# Protoboard_MX4-7-6-ESP12.net
KiCad netlist of a schematic drawn in EAGLE
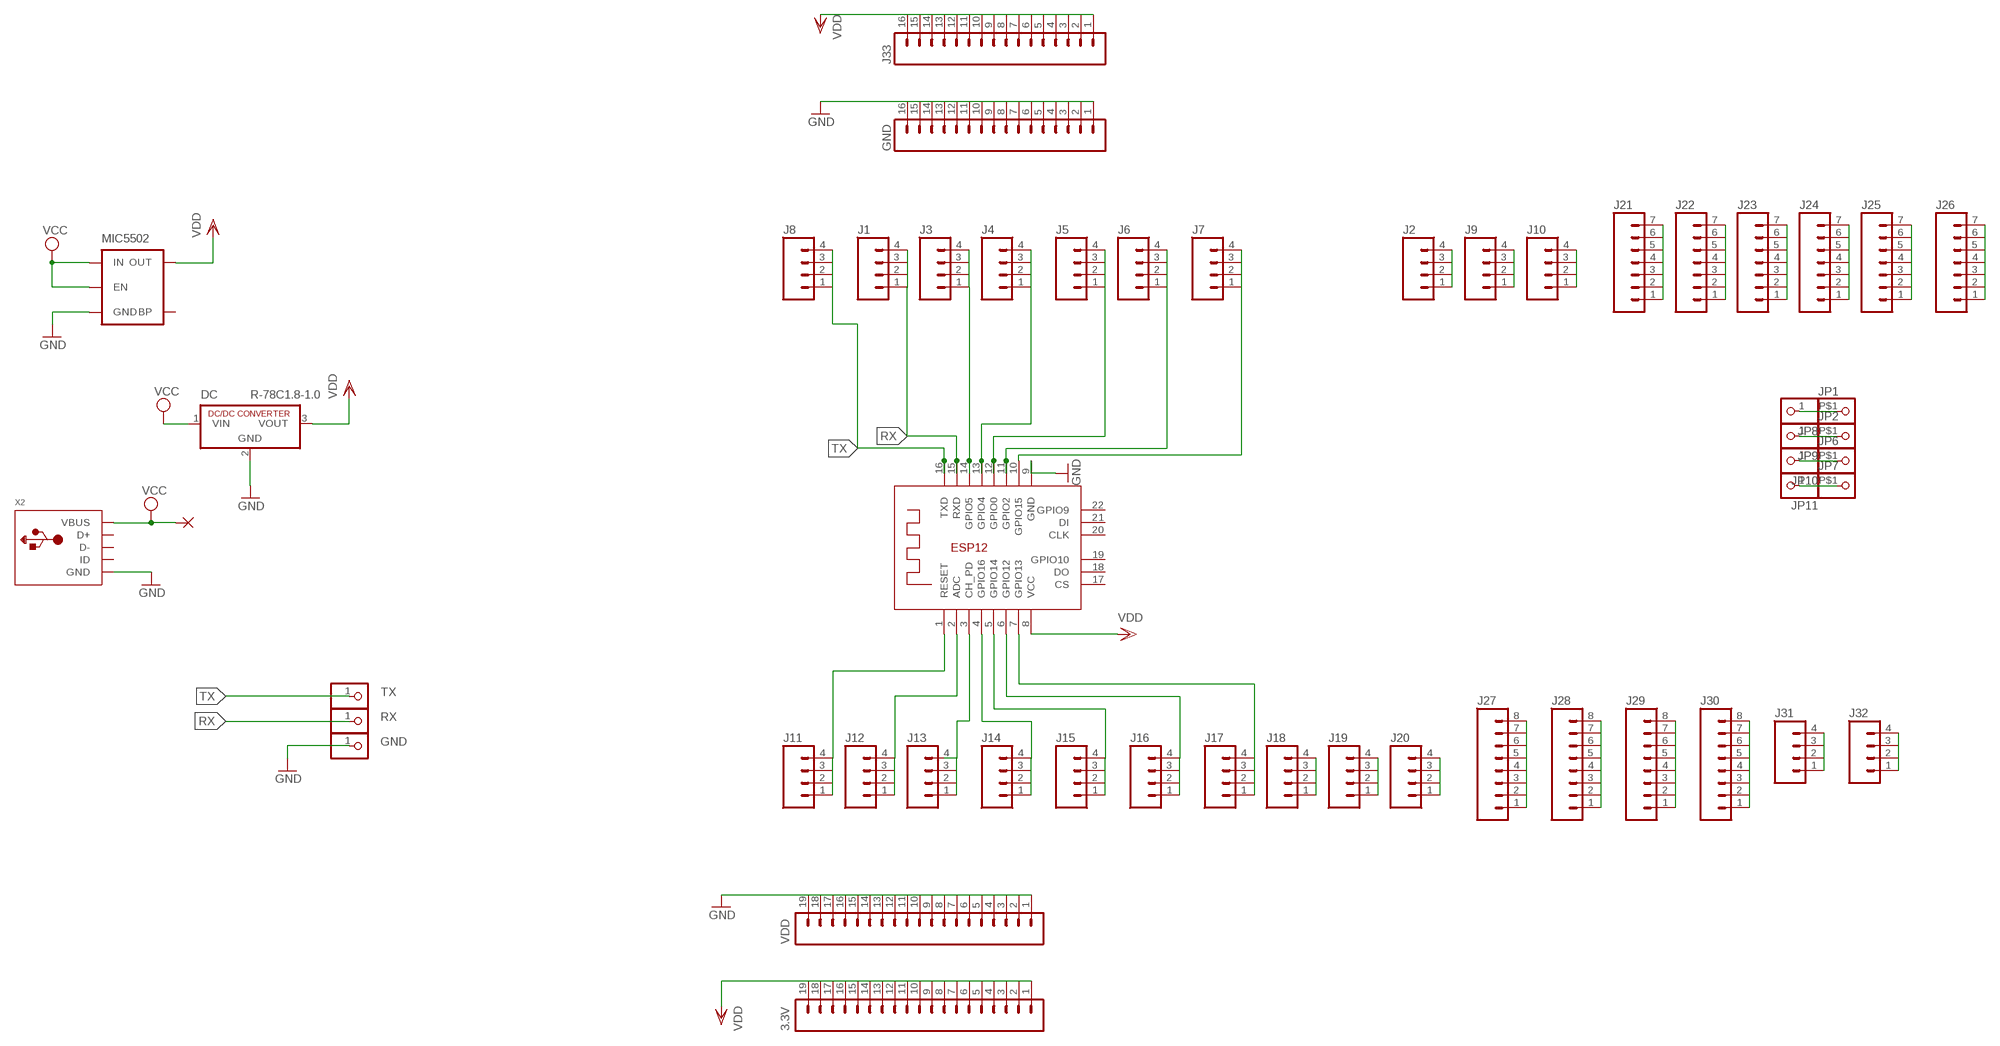
[diagram p0: schematic, sheet 1]

(export (version "E")
  (design (tool "Eeschema 10.0.6"))
  (components
    (comp (ref "3.3V")
      (value "M191X19_NO_SILK")
      (footprint "eagle-import:1X19_NO_SILK")
      (libsource (lib "eagle-import") (part "M191X19_NO_SILK"))
    )
    (comp (ref "5V")
      (value "1,6/0,8")
      (footprint "eagle-import:1,6_0,8")
      (libsource (lib "eagle-import") (part "1,6/0,8"))
    )
    (comp (ref "DC")
      (value "R-78C1.8-1.0")
      (footprint "eagle-import:SIP3")
      (libsource (lib "eagle-import") (part "R-78C-1.01.8"))
    )
    (comp (ref "GND")
      (value "M161X16_NO_SILK")
      (footprint "eagle-import:1X16_NO_SILK")
      (libsource (lib "eagle-import") (part "M161X16_NO_SILK"))
    )
    (comp (ref "J1")
      (value "M04NO_SILK_ALL_ROUND")
      (footprint "eagle-import:1X04_NO_SILK_ALL_ROUND")
      (libsource (lib "eagle-import") (part "M04NO_SILK_ALL_ROUND"))
    )
    (comp (ref "J2")
      (value "M04NO_SILK_ALL_ROUND")
      (footprint "eagle-import:1X04_NO_SILK_ALL_ROUND")
      (libsource (lib "eagle-import") (part "M04NO_SILK_ALL_ROUND"))
    )
    (comp (ref "J3")
      (value "M04NO_SILK_ALL_ROUND")
      (footprint "eagle-import:1X04_NO_SILK_ALL_ROUND")
      (libsource (lib "eagle-import") (part "M04NO_SILK_ALL_ROUND"))
    )
    (comp (ref "J4")
      (value "M04NO_SILK_ALL_ROUND")
      (footprint "eagle-import:1X04_NO_SILK_ALL_ROUND")
      (libsource (lib "eagle-import") (part "M04NO_SILK_ALL_ROUND"))
    )
    (comp (ref "J5")
      (value "M04NO_SILK_ALL_ROUND")
      (footprint "eagle-import:1X04_NO_SILK_ALL_ROUND")
      (libsource (lib "eagle-import") (part "M04NO_SILK_ALL_ROUND"))
    )
    (comp (ref "J6")
      (value "M04NO_SILK_ALL_ROUND")
      (footprint "eagle-import:1X04_NO_SILK_ALL_ROUND")
      (libsource (lib "eagle-import") (part "M04NO_SILK_ALL_ROUND"))
    )
    (comp (ref "J7")
      (value "M04NO_SILK_ALL_ROUND")
      (footprint "eagle-import:1X04_NO_SILK_ALL_ROUND")
      (libsource (lib "eagle-import") (part "M04NO_SILK_ALL_ROUND"))
    )
    (comp (ref "J8")
      (value "M04NO_SILK_ALL_ROUND")
      (footprint "eagle-import:1X04_NO_SILK_ALL_ROUND")
      (libsource (lib "eagle-import") (part "M04NO_SILK_ALL_ROUND"))
    )
    (comp (ref "J9")
      (value "M04NO_SILK_ALL_ROUND")
      (footprint "eagle-import:1X04_NO_SILK_ALL_ROUND")
      (libsource (lib "eagle-import") (part "M04NO_SILK_ALL_ROUND"))
    )
    (comp (ref "J10")
      (value "M04NO_SILK_ALL_ROUND")
      (footprint "eagle-import:1X04_NO_SILK_ALL_ROUND")
      (libsource (lib "eagle-import") (part "M04NO_SILK_ALL_ROUND"))
    )
    (comp (ref "J11")
      (value "M04NO_SILK_ALL_ROUND")
      (footprint "eagle-import:1X04_NO_SILK_ALL_ROUND")
      (libsource (lib "eagle-import") (part "M04NO_SILK_ALL_ROUND"))
    )
    (comp (ref "J12")
      (value "M04NO_SILK_ALL_ROUND")
      (footprint "eagle-import:1X04_NO_SILK_ALL_ROUND")
      (libsource (lib "eagle-import") (part "M04NO_SILK_ALL_ROUND"))
    )
    (comp (ref "J13")
      (value "M04NO_SILK_ALL_ROUND")
      (footprint "eagle-import:1X04_NO_SILK_ALL_ROUND")
      (libsource (lib "eagle-import") (part "M04NO_SILK_ALL_ROUND"))
    )
    (comp (ref "J14")
      (value "M04NO_SILK_ALL_ROUND")
      (footprint "eagle-import:1X04_NO_SILK_ALL_ROUND")
      (libsource (lib "eagle-import") (part "M04NO_SILK_ALL_ROUND"))
    )
    (comp (ref "J15")
      (value "M04NO_SILK_ALL_ROUND")
      (footprint "eagle-import:1X04_NO_SILK_ALL_ROUND")
      (libsource (lib "eagle-import") (part "M04NO_SILK_ALL_ROUND"))
    )
    (comp (ref "J16")
      (value "M04NO_SILK_ALL_ROUND")
      (footprint "eagle-import:1X04_NO_SILK_ALL_ROUND")
      (libsource (lib "eagle-import") (part "M04NO_SILK_ALL_ROUND"))
    )
    (comp (ref "J17")
      (value "M04NO_SILK_ALL_ROUND")
      (footprint "eagle-import:1X04_NO_SILK_ALL_ROUND")
      (libsource (lib "eagle-import") (part "M04NO_SILK_ALL_ROUND"))
    )
    (comp (ref "J18")
      (value "M04NO_SILK_ALL_ROUND")
      (footprint "eagle-import:1X04_NO_SILK_ALL_ROUND")
      (libsource (lib "eagle-import") (part "M04NO_SILK_ALL_ROUND"))
    )
    (comp (ref "J19")
      (value "M04NO_SILK_ALL_ROUND")
      (footprint "eagle-import:1X04_NO_SILK_ALL_ROUND")
      (libsource (lib "eagle-import") (part "M04NO_SILK_ALL_ROUND"))
    )
    (comp (ref "J20")
      (value "M04NO_SILK_ALL_ROUND")
      (footprint "eagle-import:1X04_NO_SILK_ALL_ROUND")
      (libsource (lib "eagle-import") (part "M04NO_SILK_ALL_ROUND"))
    )
    (comp (ref "J21")
      (value "M07NO_SILK")
      (footprint "eagle-import:1X07_NO_SILK")
      (libsource (lib "eagle-import") (part "M07NO_SILK"))
    )
    (comp (ref "J22")
      (value "M07NO_SILK")
      (footprint "eagle-import:1X07_NO_SILK")
      (libsource (lib "eagle-import") (part "M07NO_SILK"))
    )
    (comp (ref "J23")
      (value "M07NO_SILK")
      (footprint "eagle-import:1X07_NO_SILK")
      (libsource (lib "eagle-import") (part "M07NO_SILK"))
    )
    (comp (ref "J24")
      (value "M07NO_SILK")
      (footprint "eagle-import:1X07_NO_SILK")
      (libsource (lib "eagle-import") (part "M07NO_SILK"))
    )
    (comp (ref "J25")
      (value "M07NO_SILK")
      (footprint "eagle-import:1X07_NO_SILK")
      (libsource (lib "eagle-import") (part "M07NO_SILK"))
    )
    (comp (ref "J26")
      (value "M07NO_SILK")
      (footprint "eagle-import:1X07_NO_SILK")
      (libsource (lib "eagle-import") (part "M07NO_SILK"))
    )
    (comp (ref "J27")
      (value "M08NO_SILK_FEMALE_PTH")
      (footprint "eagle-import:1X08_NO_SILK")
      (libsource (lib "eagle-import") (part "M08NO_SILK_FEMALE_PTH"))
    )
    (comp (ref "J28")
      (value "M08NO_SILK_FEMALE_PTH")
      (footprint "eagle-import:1X08_NO_SILK")
      (libsource (lib "eagle-import") (part "M08NO_SILK_FEMALE_PTH"))
    )
    (comp (ref "J29")
      (value "M08NO_SILK_FEMALE_PTH")
      (footprint "eagle-import:1X08_NO_SILK")
      (libsource (lib "eagle-import") (part "M08NO_SILK_FEMALE_PTH"))
    )
    (comp (ref "J30")
      (value "M08NO_SILK_FEMALE_PTH")
      (footprint "eagle-import:1X08_NO_SILK")
      (libsource (lib "eagle-import") (part "M08NO_SILK_FEMALE_PTH"))
    )
    (comp (ref "J31")
      (value "M04NO_SILK_ALL_ROUND")
      (footprint "eagle-import:1X04_NO_SILK_ALL_ROUND")
      (libsource (lib "eagle-import") (part "M04NO_SILK_ALL_ROUND"))
    )
    (comp (ref "J32")
      (value "M04NO_SILK_ALL_ROUND")
      (footprint "eagle-import:1X04_NO_SILK_ALL_ROUND")
      (libsource (lib "eagle-import") (part "M04NO_SILK_ALL_ROUND"))
    )
    (comp (ref "J33")
      (value "M161X16_NO_SILK")
      (footprint "eagle-import:1X16_NO_SILK")
      (libsource (lib "eagle-import") (part "M161X16_NO_SILK"))
    )
    (comp (ref "JP1")
      (value "PINHD-1X1-BIGPOGO")
      (footprint "eagle-import:1X1-BIGPOGO")
      (libsource (lib "eagle-import") (part "PINHD-1X1-BIGPOGO"))
    )
    (comp (ref "JP2")
      (value "PINHD-1X1-BIGPOGO")
      (footprint "eagle-import:1X1-BIGPOGO")
      (libsource (lib "eagle-import") (part "PINHD-1X1-BIGPOGO"))
    )
    (comp (ref "JP3")
      (value "TX")
      (footprint "eagle-import:1X01-CLEANBIG")
      (libsource (lib "eagle-import") (part "PINHD-1X1CB"))
    )
    (comp (ref "JP4")
      (value "RX")
      (footprint "eagle-import:1X01-CLEANBIG")
      (libsource (lib "eagle-import") (part "PINHD-1X1CB"))
    )
    (comp (ref "JP5")
      (value "GND")
      (footprint "eagle-import:1X01-CLEANBIG")
      (libsource (lib "eagle-import") (part "PINHD-1X1CB"))
    )
    (comp (ref "JP6")
      (value "PINHD-1X1-BIGPOGO")
      (footprint "eagle-import:1X1-BIGPOGO")
      (libsource (lib "eagle-import") (part "PINHD-1X1-BIGPOGO"))
    )
    (comp (ref "JP7")
      (value "PINHD-1X1-BIGPOGO")
      (footprint "eagle-import:1X1-BIGPOGO")
      (libsource (lib "eagle-import") (part "PINHD-1X1-BIGPOGO"))
    )
    (comp (ref "JP8")
      (value "PINHD-1X1CB")
      (footprint "eagle-import:1X01-CLEANBIG")
      (libsource (lib "eagle-import") (part "PINHD-1X1CB"))
    )
    (comp (ref "JP9")
      (value "PINHD-1X1CB")
      (footprint "eagle-import:1X01-CLEANBIG")
      (libsource (lib "eagle-import") (part "PINHD-1X1CB"))
    )
    (comp (ref "JP10")
      (value "PINHD-1X1CB")
      (footprint "eagle-import:1X01-CLEANBIG")
      (libsource (lib "eagle-import") (part "PINHD-1X1CB"))
    )
    (comp (ref "JP11")
      (value "PINHD-1X1CB")
      (footprint "eagle-import:1X01-CLEANBIG")
      (libsource (lib "eagle-import") (part "PINHD-1X1CB"))
    )
    (comp (ref "MIC5502")
      (value "MIC52053.3V")
      (footprint "eagle-import:SOT23-5")
      (libsource (lib "eagle-import") (part "MIC52053.3V"))
    )
    (comp (ref "VDD")
      (value "M191X19_NO_SILK")
      (footprint "eagle-import:1X19_NO_SILK")
      (libsource (lib "eagle-import") (part "M191X19_NO_SILK"))
    )
    (comp (ref "X1")
      (value "ESP-12E")
      (footprint "eagle-import:ESP-12E")
      (libsource (lib "eagle-import") (part "ESP-12E"))
    )
    (comp (ref "X2")
      (value "USBMICRO_20329")
      (footprint "eagle-import:4UCONN_20329")
      (libsource (lib "eagle-import") (part "USBMICRO_20329"))
    )
  )
  (nets
    (net (code "1") (name "GND") (class "Default")
      (node (ref "DC") (pin "2") (pinfunction "GND_2") (pintype "passive"))
      (node (ref "GND") (pin "1") (pinfunction "1_1") (pintype "passive"))
      (node (ref "GND") (pin "10") (pinfunction "10_10") (pintype "passive"))
      (node (ref "GND") (pin "11") (pinfunction "11_11") (pintype "passive"))
      (node (ref "GND") (pin "12") (pinfunction "12_12") (pintype "passive"))
      (node (ref "GND") (pin "13") (pinfunction "13_13") (pintype "passive"))
      (node (ref "GND") (pin "14") (pinfunction "14_14") (pintype "passive"))
      (node (ref "GND") (pin "15") (pinfunction "15_15") (pintype "passive"))
      (node (ref "GND") (pin "16") (pinfunction "16_16") (pintype "passive"))
      (node (ref "GND") (pin "2") (pinfunction "2_2") (pintype "passive"))
      (node (ref "GND") (pin "3") (pinfunction "3_3") (pintype "passive"))
      (node (ref "GND") (pin "4") (pinfunction "4_4") (pintype "passive"))
      (node (ref "GND") (pin "5") (pinfunction "5_5") (pintype "passive"))
      (node (ref "GND") (pin "6") (pinfunction "6_6") (pintype "passive"))
      (node (ref "GND") (pin "7") (pinfunction "7_7") (pintype "passive"))
      (node (ref "GND") (pin "8") (pinfunction "8_8") (pintype "passive"))
      (node (ref "GND") (pin "9") (pinfunction "9_9") (pintype "passive"))
      (node (ref "JP5") (pin "1") (pinfunction "1_1") (pintype "passive"))
      (node (ref "MIC5502") (pin "2") (pinfunction "GND_2") (pintype "input"))
      (node (ref "VDD") (pin "1") (pinfunction "1_1") (pintype "passive"))
      (node (ref "VDD") (pin "10") (pinfunction "10_10") (pintype "passive"))
      (node (ref "VDD") (pin "11") (pinfunction "11_11") (pintype "passive"))
      (node (ref "VDD") (pin "12") (pinfunction "12_12") (pintype "passive"))
      (node (ref "VDD") (pin "13") (pinfunction "13_13") (pintype "passive"))
      (node (ref "VDD") (pin "14") (pinfunction "14_14") (pintype "passive"))
      (node (ref "VDD") (pin "15") (pinfunction "15_15") (pintype "passive"))
      (node (ref "VDD") (pin "16") (pinfunction "16_16") (pintype "passive"))
      (node (ref "VDD") (pin "17") (pinfunction "17_17") (pintype "passive"))
      (node (ref "VDD") (pin "18") (pinfunction "18_18") (pintype "passive"))
      (node (ref "VDD") (pin "19") (pinfunction "19_19") (pintype "passive"))
      (node (ref "VDD") (pin "2") (pinfunction "2_2") (pintype "passive"))
      (node (ref "VDD") (pin "3") (pinfunction "3_3") (pintype "passive"))
      (node (ref "VDD") (pin "4") (pinfunction "4_4") (pintype "passive"))
      (node (ref "VDD") (pin "5") (pinfunction "5_5") (pintype "passive"))
      (node (ref "VDD") (pin "6") (pinfunction "6_6") (pintype "passive"))
      (node (ref "VDD") (pin "7") (pinfunction "7_7") (pintype "passive"))
      (node (ref "VDD") (pin "8") (pinfunction "8_8") (pintype "passive"))
      (node (ref "VDD") (pin "9") (pinfunction "9_9") (pintype "passive"))
      (node (ref "X1") (pin "9") (pinfunction "GND_9") (pintype "power_in"))
      (node (ref "X2") (pin "BASE@1") (pinfunction "GND_BASE@1") (pintype "power_in"))
      (node (ref "X2") (pin "BASE@2") (pinfunction "GND_BASE@2") (pintype "power_in"))
      (node (ref "X2") (pin "GND") (pinfunction "GND_GND") (pintype "power_in"))
      (node (ref "X2") (pin "SPRT@1") (pinfunction "GND_SPRT@1") (pintype "power_in"))
      (node (ref "X2") (pin "SPRT@2") (pinfunction "GND_SPRT@2") (pintype "power_in"))
      (node (ref "X2") (pin "SPRT@3") (pinfunction "GND_SPRT@3") (pintype "power_in"))
      (node (ref "X2") (pin "SPRT@4") (pinfunction "GND_SPRT@4") (pintype "power_in"))
    )
    (net (code "2") (name "Net-(J2-Pad1)") (class "Default")
      (node (ref "J2") (pin "1") (pinfunction "1_1") (pintype "passive"))
      (node (ref "J2") (pin "2") (pinfunction "2_2") (pintype "passive"))
      (node (ref "J2") (pin "3") (pinfunction "3_3") (pintype "passive"))
      (node (ref "J2") (pin "4") (pinfunction "4_4") (pintype "passive"))
    )
    (net (code "3") (name "Net-(J9-Pad1)") (class "Default")
      (node (ref "J9") (pin "1") (pinfunction "1_1") (pintype "passive"))
      (node (ref "J9") (pin "2") (pinfunction "2_2") (pintype "passive"))
      (node (ref "J9") (pin "3") (pinfunction "3_3") (pintype "passive"))
      (node (ref "J9") (pin "4") (pinfunction "4_4") (pintype "passive"))
    )
    (net (code "4") (name "Net-(J10-Pad1)") (class "Default")
      (node (ref "J10") (pin "1") (pinfunction "1_1") (pintype "passive"))
      (node (ref "J10") (pin "2") (pinfunction "2_2") (pintype "passive"))
      (node (ref "J10") (pin "3") (pinfunction "3_3") (pintype "passive"))
      (node (ref "J10") (pin "4") (pinfunction "4_4") (pintype "passive"))
    )
    (net (code "5") (name "Net-(J18-Pad1)") (class "Default")
      (node (ref "J18") (pin "1") (pinfunction "1_1") (pintype "passive"))
      (node (ref "J18") (pin "2") (pinfunction "2_2") (pintype "passive"))
      (node (ref "J18") (pin "3") (pinfunction "3_3") (pintype "passive"))
      (node (ref "J18") (pin "4") (pinfunction "4_4") (pintype "passive"))
    )
    (net (code "6") (name "Net-(J19-Pad1)") (class "Default")
      (node (ref "J19") (pin "1") (pinfunction "1_1") (pintype "passive"))
      (node (ref "J19") (pin "2") (pinfunction "2_2") (pintype "passive"))
      (node (ref "J19") (pin "3") (pinfunction "3_3") (pintype "passive"))
      (node (ref "J19") (pin "4") (pinfunction "4_4") (pintype "passive"))
    )
    (net (code "7") (name "Net-(J20-Pad1)") (class "Default")
      (node (ref "J20") (pin "1") (pinfunction "1_1") (pintype "passive"))
      (node (ref "J20") (pin "2") (pinfunction "2_2") (pintype "passive"))
      (node (ref "J20") (pin "3") (pinfunction "3_3") (pintype "passive"))
      (node (ref "J20") (pin "4") (pinfunction "4_4") (pintype "passive"))
    )
    (net (code "8") (name "Net-(J21-Pad1)") (class "Default")
      (node (ref "J21") (pin "1") (pinfunction "1_1") (pintype "passive"))
      (node (ref "J21") (pin "2") (pinfunction "2_2") (pintype "passive"))
      (node (ref "J21") (pin "3") (pinfunction "3_3") (pintype "passive"))
      (node (ref "J21") (pin "4") (pinfunction "4_4") (pintype "passive"))
      (node (ref "J21") (pin "5") (pinfunction "5_5") (pintype "passive"))
      (node (ref "J21") (pin "6") (pinfunction "6_6") (pintype "passive"))
      (node (ref "J21") (pin "7") (pinfunction "7_7") (pintype "passive"))
    )
    (net (code "9") (name "Net-(J22-Pad1)") (class "Default")
      (node (ref "J22") (pin "1") (pinfunction "1_1") (pintype "passive"))
      (node (ref "J22") (pin "2") (pinfunction "2_2") (pintype "passive"))
      (node (ref "J22") (pin "3") (pinfunction "3_3") (pintype "passive"))
      (node (ref "J22") (pin "4") (pinfunction "4_4") (pintype "passive"))
      (node (ref "J22") (pin "5") (pinfunction "5_5") (pintype "passive"))
      (node (ref "J22") (pin "6") (pinfunction "6_6") (pintype "passive"))
      (node (ref "J22") (pin "7") (pinfunction "7_7") (pintype "passive"))
    )
    (net (code "10") (name "Net-(J23-Pad1)") (class "Default")
      (node (ref "J23") (pin "1") (pinfunction "1_1") (pintype "passive"))
      (node (ref "J23") (pin "2") (pinfunction "2_2") (pintype "passive"))
      (node (ref "J23") (pin "3") (pinfunction "3_3") (pintype "passive"))
      (node (ref "J23") (pin "4") (pinfunction "4_4") (pintype "passive"))
      (node (ref "J23") (pin "5") (pinfunction "5_5") (pintype "passive"))
      (node (ref "J23") (pin "6") (pinfunction "6_6") (pintype "passive"))
      (node (ref "J23") (pin "7") (pinfunction "7_7") (pintype "passive"))
    )
    (net (code "11") (name "Net-(J24-Pad1)") (class "Default")
      (node (ref "J24") (pin "1") (pinfunction "1_1") (pintype "passive"))
      (node (ref "J24") (pin "2") (pinfunction "2_2") (pintype "passive"))
      (node (ref "J24") (pin "3") (pinfunction "3_3") (pintype "passive"))
      (node (ref "J24") (pin "4") (pinfunction "4_4") (pintype "passive"))
      (node (ref "J24") (pin "5") (pinfunction "5_5") (pintype "passive"))
      (node (ref "J24") (pin "6") (pinfunction "6_6") (pintype "passive"))
      (node (ref "J24") (pin "7") (pinfunction "7_7") (pintype "passive"))
    )
    (net (code "12") (name "Net-(J25-Pad1)") (class "Default")
      (node (ref "J25") (pin "1") (pinfunction "1_1") (pintype "passive"))
      (node (ref "J25") (pin "2") (pinfunction "2_2") (pintype "passive"))
      (node (ref "J25") (pin "3") (pinfunction "3_3") (pintype "passive"))
      (node (ref "J25") (pin "4") (pinfunction "4_4") (pintype "passive"))
      (node (ref "J25") (pin "5") (pinfunction "5_5") (pintype "passive"))
      (node (ref "J25") (pin "6") (pinfunction "6_6") (pintype "passive"))
      (node (ref "J25") (pin "7") (pinfunction "7_7") (pintype "passive"))
    )
    (net (code "13") (name "Net-(J26-Pad1)") (class "Default")
      (node (ref "J26") (pin "1") (pinfunction "1_1") (pintype "passive"))
      (node (ref "J26") (pin "2") (pinfunction "2_2") (pintype "passive"))
      (node (ref "J26") (pin "3") (pinfunction "3_3") (pintype "passive"))
      (node (ref "J26") (pin "4") (pinfunction "4_4") (pintype "passive"))
      (node (ref "J26") (pin "5") (pinfunction "5_5") (pintype "passive"))
      (node (ref "J26") (pin "6") (pinfunction "6_6") (pintype "passive"))
      (node (ref "J26") (pin "7") (pinfunction "7_7") (pintype "passive"))
    )
    (net (code "14") (name "Net-(J27-Pad1)") (class "Default")
      (node (ref "J27") (pin "1") (pinfunction "1_1") (pintype "passive"))
      (node (ref "J27") (pin "2") (pinfunction "2_2") (pintype "passive"))
      (node (ref "J27") (pin "3") (pinfunction "3_3") (pintype "passive"))
      (node (ref "J27") (pin "4") (pinfunction "4_4") (pintype "passive"))
      (node (ref "J27") (pin "5") (pinfunction "5_5") (pintype "passive"))
      (node (ref "J27") (pin "6") (pinfunction "6_6") (pintype "passive"))
      (node (ref "J27") (pin "7") (pinfunction "7_7") (pintype "passive"))
      (node (ref "J27") (pin "8") (pinfunction "8_8") (pintype "passive"))
    )
    (net (code "15") (name "Net-(J28-Pad1)") (class "Default")
      (node (ref "J28") (pin "1") (pinfunction "1_1") (pintype "passive"))
      (node (ref "J28") (pin "2") (pinfunction "2_2") (pintype "passive"))
      (node (ref "J28") (pin "3") (pinfunction "3_3") (pintype "passive"))
      (node (ref "J28") (pin "4") (pinfunction "4_4") (pintype "passive"))
      (node (ref "J28") (pin "5") (pinfunction "5_5") (pintype "passive"))
      (node (ref "J28") (pin "6") (pinfunction "6_6") (pintype "passive"))
      (node (ref "J28") (pin "7") (pinfunction "7_7") (pintype "passive"))
      (node (ref "J28") (pin "8") (pinfunction "8_8") (pintype "passive"))
    )
    (net (code "16") (name "Net-(J29-Pad1)") (class "Default")
      (node (ref "J29") (pin "1") (pinfunction "1_1") (pintype "passive"))
      (node (ref "J29") (pin "2") (pinfunction "2_2") (pintype "passive"))
      (node (ref "J29") (pin "3") (pinfunction "3_3") (pintype "passive"))
      (node (ref "J29") (pin "4") (pinfunction "4_4") (pintype "passive"))
      (node (ref "J29") (pin "5") (pinfunction "5_5") (pintype "passive"))
      (node (ref "J29") (pin "6") (pinfunction "6_6") (pintype "passive"))
      (node (ref "J29") (pin "7") (pinfunction "7_7") (pintype "passive"))
      (node (ref "J29") (pin "8") (pinfunction "8_8") (pintype "passive"))
    )
    (net (code "17") (name "Net-(J30-Pad1)") (class "Default")
      (node (ref "J30") (pin "1") (pinfunction "1_1") (pintype "passive"))
      (node (ref "J30") (pin "2") (pinfunction "2_2") (pintype "passive"))
      (node (ref "J30") (pin "3") (pinfunction "3_3") (pintype "passive"))
      (node (ref "J30") (pin "4") (pinfunction "4_4") (pintype "passive"))
      (node (ref "J30") (pin "5") (pinfunction "5_5") (pintype "passive"))
      (node (ref "J30") (pin "6") (pinfunction "6_6") (pintype "passive"))
      (node (ref "J30") (pin "7") (pinfunction "7_7") (pintype "passive"))
      (node (ref "J30") (pin "8") (pinfunction "8_8") (pintype "passive"))
    )
    (net (code "18") (name "Net-(J31-Pad1)") (class "Default")
      (node (ref "J31") (pin "1") (pinfunction "1_1") (pintype "passive"))
      (node (ref "J31") (pin "2") (pinfunction "2_2") (pintype "passive"))
      (node (ref "J31") (pin "3") (pinfunction "3_3") (pintype "passive"))
      (node (ref "J31") (pin "4") (pinfunction "4_4") (pintype "passive"))
    )
    (net (code "19") (name "Net-(J32-Pad1)") (class "Default")
      (node (ref "J32") (pin "1") (pinfunction "1_1") (pintype "passive"))
      (node (ref "J32") (pin "2") (pinfunction "2_2") (pintype "passive"))
      (node (ref "J32") (pin "3") (pinfunction "3_3") (pintype "passive"))
      (node (ref "J32") (pin "4") (pinfunction "4_4") (pintype "passive"))
    )
    (net (code "20") (name "Net-(JP1-1)") (class "Default")
      (node (ref "JP1") (pin "P$1") (pinfunction "1_P$1") (pintype "passive"))
      (node (ref "JP8") (pin "1") (pinfunction "1_1") (pintype "passive"))
    )
    (net (code "21") (name "Net-(JP2-1)") (class "Default")
      (node (ref "JP2") (pin "P$1") (pinfunction "1_P$1") (pintype "passive"))
      (node (ref "JP9") (pin "1") (pinfunction "1_1") (pintype "passive"))
    )
    (net (code "22") (name "Net-(JP6-1)") (class "Default")
      (node (ref "JP10") (pin "1") (pinfunction "1_1") (pintype "passive"))
      (node (ref "JP6") (pin "P$1") (pinfunction "1_P$1") (pintype "passive"))
    )
    (net (code "23") (name "Net-(JP7-1)") (class "Default")
      (node (ref "JP11") (pin "1") (pinfunction "1_1") (pintype "passive"))
      (node (ref "JP7") (pin "P$1") (pinfunction "1_P$1") (pintype "passive"))
    )
    (net (code "24") (name "Net-(X1-ADC)") (class "Default")
      (node (ref "J12") (pin "1") (pinfunction "1_1") (pintype "passive"))
      (node (ref "J12") (pin "2") (pinfunction "2_2") (pintype "passive"))
      (node (ref "J12") (pin "3") (pinfunction "3_3") (pintype "passive"))
      (node (ref "J12") (pin "4") (pinfunction "4_4") (pintype "passive"))
      (node (ref "X1") (pin "2") (pinfunction "ADC_2") (pintype "passive"))
    )
    (net (code "25") (name "Net-(X1-CH_PD)") (class "Default")
      (node (ref "J13") (pin "1") (pinfunction "1_1") (pintype "passive"))
      (node (ref "J13") (pin "2") (pinfunction "2_2") (pintype "passive"))
      (node (ref "J13") (pin "3") (pinfunction "3_3") (pintype "passive"))
      (node (ref "J13") (pin "4") (pinfunction "4_4") (pintype "passive"))
      (node (ref "X1") (pin "3") (pinfunction "CH_PD_3") (pintype "input"))
    )
    (net (code "26") (name "Net-(X1-GPIO0)") (class "Default")
      (node (ref "J5") (pin "1") (pinfunction "1_1") (pintype "passive"))
      (node (ref "J5") (pin "2") (pinfunction "2_2") (pintype "passive"))
      (node (ref "J5") (pin "3") (pinfunction "3_3") (pintype "passive"))
      (node (ref "J5") (pin "4") (pinfunction "4_4") (pintype "passive"))
      (node (ref "X1") (pin "12") (pinfunction "GPIO0_12") (pintype "bidirectional"))
    )
    (net (code "27") (name "Net-(X1-GPIO2)") (class "Default")
      (node (ref "J6") (pin "1") (pinfunction "1_1") (pintype "passive"))
      (node (ref "J6") (pin "2") (pinfunction "2_2") (pintype "passive"))
      (node (ref "J6") (pin "3") (pinfunction "3_3") (pintype "passive"))
      (node (ref "J6") (pin "4") (pinfunction "4_4") (pintype "passive"))
      (node (ref "X1") (pin "11") (pinfunction "GPIO2_11") (pintype "bidirectional"))
    )
    (net (code "28") (name "Net-(X1-GPIO4)") (class "Default")
      (node (ref "J4") (pin "1") (pinfunction "1_1") (pintype "passive"))
      (node (ref "J4") (pin "2") (pinfunction "2_2") (pintype "passive"))
      (node (ref "J4") (pin "3") (pinfunction "3_3") (pintype "passive"))
      (node (ref "J4") (pin "4") (pinfunction "4_4") (pintype "passive"))
      (node (ref "X1") (pin "13") (pinfunction "GPIO4_13") (pintype "bidirectional"))
    )
    (net (code "29") (name "Net-(X1-GPIO5)") (class "Default")
      (node (ref "J3") (pin "1") (pinfunction "1_1") (pintype "passive"))
      (node (ref "J3") (pin "2") (pinfunction "2_2") (pintype "passive"))
      (node (ref "J3") (pin "3") (pinfunction "3_3") (pintype "passive"))
      (node (ref "J3") (pin "4") (pinfunction "4_4") (pintype "passive"))
      (node (ref "X1") (pin "14") (pinfunction "GPIO5_14") (pintype "bidirectional"))
    )
    (net (code "30") (name "Net-(X1-GPIO12)") (class "Default")
      (node (ref "J16") (pin "1") (pinfunction "1_1") (pintype "passive"))
      (node (ref "J16") (pin "2") (pinfunction "2_2") (pintype "passive"))
      (node (ref "J16") (pin "3") (pinfunction "3_3") (pintype "passive"))
      (node (ref "J16") (pin "4") (pinfunction "4_4") (pintype "passive"))
      (node (ref "X1") (pin "6") (pinfunction "GPIO12_6") (pintype "bidirectional"))
    )
    (net (code "31") (name "Net-(X1-GPIO13)") (class "Default")
      (node (ref "J17") (pin "1") (pinfunction "1_1") (pintype "passive"))
      (node (ref "J17") (pin "2") (pinfunction "2_2") (pintype "passive"))
      (node (ref "J17") (pin "3") (pinfunction "3_3") (pintype "passive"))
      (node (ref "J17") (pin "4") (pinfunction "4_4") (pintype "passive"))
      (node (ref "X1") (pin "7") (pinfunction "GPIO13_7") (pintype "bidirectional"))
    )
    (net (code "32") (name "Net-(X1-GPIO14)") (class "Default")
      (node (ref "J15") (pin "1") (pinfunction "1_1") (pintype "passive"))
      (node (ref "J15") (pin "2") (pinfunction "2_2") (pintype "passive"))
      (node (ref "J15") (pin "3") (pinfunction "3_3") (pintype "passive"))
      (node (ref "J15") (pin "4") (pinfunction "4_4") (pintype "passive"))
      (node (ref "X1") (pin "5") (pinfunction "GPIO14_5") (pintype "bidirectional"))
    )
    (net (code "33") (name "Net-(X1-GPIO15)") (class "Default")
      (node (ref "J7") (pin "1") (pinfunction "1_1") (pintype "passive"))
      (node (ref "J7") (pin "2") (pinfunction "2_2") (pintype "passive"))
      (node (ref "J7") (pin "3") (pinfunction "3_3") (pintype "passive"))
      (node (ref "J7") (pin "4") (pinfunction "4_4") (pintype "passive"))
      (node (ref "X1") (pin "10") (pinfunction "GPIO15_10") (pintype "bidirectional"))
    )
    (net (code "34") (name "Net-(X1-GPIO16)") (class "Default")
      (node (ref "J14") (pin "1") (pinfunction "1_1") (pintype "passive"))
      (node (ref "J14") (pin "2") (pinfunction "2_2") (pintype "passive"))
      (node (ref "J14") (pin "3") (pinfunction "3_3") (pintype "passive"))
      (node (ref "J14") (pin "4") (pinfunction "4_4") (pintype "passive"))
      (node (ref "X1") (pin "4") (pinfunction "GPIO16_4") (pintype "bidirectional"))
    )
    (net (code "35") (name "Net-(X1-RESET)") (class "Default")
      (node (ref "J11") (pin "1") (pinfunction "1_1") (pintype "passive"))
      (node (ref "J11") (pin "2") (pinfunction "2_2") (pintype "passive"))
      (node (ref "J11") (pin "3") (pinfunction "3_3") (pintype "passive"))
      (node (ref "J11") (pin "4") (pinfunction "4_4") (pintype "passive"))
      (node (ref "X1") (pin "1") (pinfunction "RESET_1") (pintype "input"))
    )
    (net (code "36") (name "RX") (class "Default")
      (node (ref "J1") (pin "1") (pinfunction "1_1") (pintype "passive"))
      (node (ref "J1") (pin "2") (pinfunction "2_2") (pintype "passive"))
      (node (ref "J1") (pin "3") (pinfunction "3_3") (pintype "passive"))
      (node (ref "J1") (pin "4") (pinfunction "4_4") (pintype "passive"))
      (node (ref "JP4") (pin "1") (pinfunction "1_1") (pintype "passive"))
      (node (ref "X1") (pin "15") (pinfunction "RXD_15") (pintype "input"))
    )
    (net (code "37") (name "TX") (class "Default")
      (node (ref "J8") (pin "1") (pinfunction "1_1") (pintype "passive"))
      (node (ref "J8") (pin "2") (pinfunction "2_2") (pintype "passive"))
      (node (ref "J8") (pin "3") (pinfunction "3_3") (pintype "passive"))
      (node (ref "J8") (pin "4") (pinfunction "4_4") (pintype "passive"))
      (node (ref "JP3") (pin "1") (pinfunction "1_1") (pintype "passive"))
      (node (ref "X1") (pin "16") (pinfunction "TXD_16") (pintype "output"))
    )
    (net (code "38") (name "VCC") (class "Default")
      (node (ref "5V") (pin "1") (pinfunction "P_1") (pintype "passive"))
      (node (ref "DC") (pin "1") (pinfunction "VIN_1") (pintype "passive"))
      (node (ref "MIC5502") (pin "1") (pinfunction "IN_1") (pintype "input"))
      (node (ref "MIC5502") (pin "3") (pinfunction "EN_3") (pintype "input"))
      (node (ref "X2") (pin "VBUS") (pinfunction "VBUS_VBUS") (pintype "power_in"))
    )
    (net (code "39") (name "VDD") (class "Default")
      (node (ref "3.3V") (pin "1") (pinfunction "1_1") (pintype "passive"))
      (node (ref "3.3V") (pin "10") (pinfunction "10_10") (pintype "passive"))
      (node (ref "3.3V") (pin "11") (pinfunction "11_11") (pintype "passive"))
      (node (ref "3.3V") (pin "12") (pinfunction "12_12") (pintype "passive"))
      (node (ref "3.3V") (pin "13") (pinfunction "13_13") (pintype "passive"))
      (node (ref "3.3V") (pin "14") (pinfunction "14_14") (pintype "passive"))
      (node (ref "3.3V") (pin "15") (pinfunction "15_15") (pintype "passive"))
      (node (ref "3.3V") (pin "16") (pinfunction "16_16") (pintype "passive"))
      (node (ref "3.3V") (pin "17") (pinfunction "17_17") (pintype "passive"))
      (node (ref "3.3V") (pin "18") (pinfunction "18_18") (pintype "passive"))
      (node (ref "3.3V") (pin "19") (pinfunction "19_19") (pintype "passive"))
      (node (ref "3.3V") (pin "2") (pinfunction "2_2") (pintype "passive"))
      (node (ref "3.3V") (pin "3") (pinfunction "3_3") (pintype "passive"))
      (node (ref "3.3V") (pin "4") (pinfunction "4_4") (pintype "passive"))
      (node (ref "3.3V") (pin "5") (pinfunction "5_5") (pintype "passive"))
      (node (ref "3.3V") (pin "6") (pinfunction "6_6") (pintype "passive"))
      (node (ref "3.3V") (pin "7") (pinfunction "7_7") (pintype "passive"))
      (node (ref "3.3V") (pin "8") (pinfunction "8_8") (pintype "passive"))
      (node (ref "3.3V") (pin "9") (pinfunction "9_9") (pintype "passive"))
      (node (ref "DC") (pin "3") (pinfunction "VOUT_3") (pintype "passive"))
      (node (ref "J33") (pin "1") (pinfunction "1_1") (pintype "passive"))
      (node (ref "J33") (pin "10") (pinfunction "10_10") (pintype "passive"))
      (node (ref "J33") (pin "11") (pinfunction "11_11") (pintype "passive"))
      (node (ref "J33") (pin "12") (pinfunction "12_12") (pintype "passive"))
      (node (ref "J33") (pin "13") (pinfunction "13_13") (pintype "passive"))
      (node (ref "J33") (pin "14") (pinfunction "14_14") (pintype "passive"))
      (node (ref "J33") (pin "15") (pinfunction "15_15") (pintype "passive"))
      (node (ref "J33") (pin "16") (pinfunction "16_16") (pintype "passive"))
      (node (ref "J33") (pin "2") (pinfunction "2_2") (pintype "passive"))
      (node (ref "J33") (pin "3") (pinfunction "3_3") (pintype "passive"))
      (node (ref "J33") (pin "4") (pinfunction "4_4") (pintype "passive"))
      (node (ref "J33") (pin "5") (pinfunction "5_5") (pintype "passive"))
      (node (ref "J33") (pin "6") (pinfunction "6_6") (pintype "passive"))
      (node (ref "J33") (pin "7") (pinfunction "7_7") (pintype "passive"))
      (node (ref "J33") (pin "8") (pinfunction "8_8") (pintype "passive"))
      (node (ref "J33") (pin "9") (pinfunction "9_9") (pintype "passive"))
      (node (ref "MIC5502") (pin "5") (pinfunction "OUT_5") (pintype "passive"))
      (node (ref "X1") (pin "8") (pinfunction "VCC_8") (pintype "power_in"))
    )
    (net (code "40") (name "unconnected-(MIC5502-BP-Pad4)") (class "Default")
      (node (ref "MIC5502") (pin "4") (pinfunction "BP_4") (pintype "input"))
    )
    (net (code "41") (name "unconnected-(X1-CLK-Pad20)") (class "Default")
      (node (ref "X1") (pin "20") (pinfunction "CLK_20") (pintype "bidirectional"))
    )
    (net (code "42") (name "unconnected-(X1-CS-Pad17)") (class "Default")
      (node (ref "X1") (pin "17") (pinfunction "CS_17") (pintype "bidirectional"))
    )
    (net (code "43") (name "unconnected-(X1-DI-Pad21)") (class "Default")
      (node (ref "X1") (pin "21") (pinfunction "DI_21") (pintype "bidirectional"))
    )
    (net (code "44") (name "unconnected-(X1-DO-Pad18)") (class "Default")
      (node (ref "X1") (pin "18") (pinfunction "DO_18") (pintype "bidirectional"))
    )
    (net (code "45") (name "unconnected-(X1-GPIO9-Pad22)") (class "Default")
      (node (ref "X1") (pin "22") (pinfunction "GPIO9_22") (pintype "bidirectional"))
    )
    (net (code "46") (name "unconnected-(X1-GPIO10-Pad19)") (class "Default")
      (node (ref "X1") (pin "19") (pinfunction "GPIO10_19") (pintype "bidirectional"))
    )
    (net (code "47") (name "unconnected-(X2-PadD+)") (class "Default")
      (node (ref "X2") (pin "D+") (pinfunction "D+_D+") (pintype "bidirectional"))
    )
    (net (code "48") (name "unconnected-(X2-PadD-)") (class "Default")
      (node (ref "X2") (pin "D-") (pinfunction "D-_D-") (pintype "bidirectional"))
    )
    (net (code "49") (name "unconnected-(X2-PadID)") (class "Default")
      (node (ref "X2") (pin "ID") (pinfunction "ID_ID") (pintype "bidirectional"))
    )
  )
)
